# feu_35.net
KiCad netlist of a schematic drawn in EAGLE
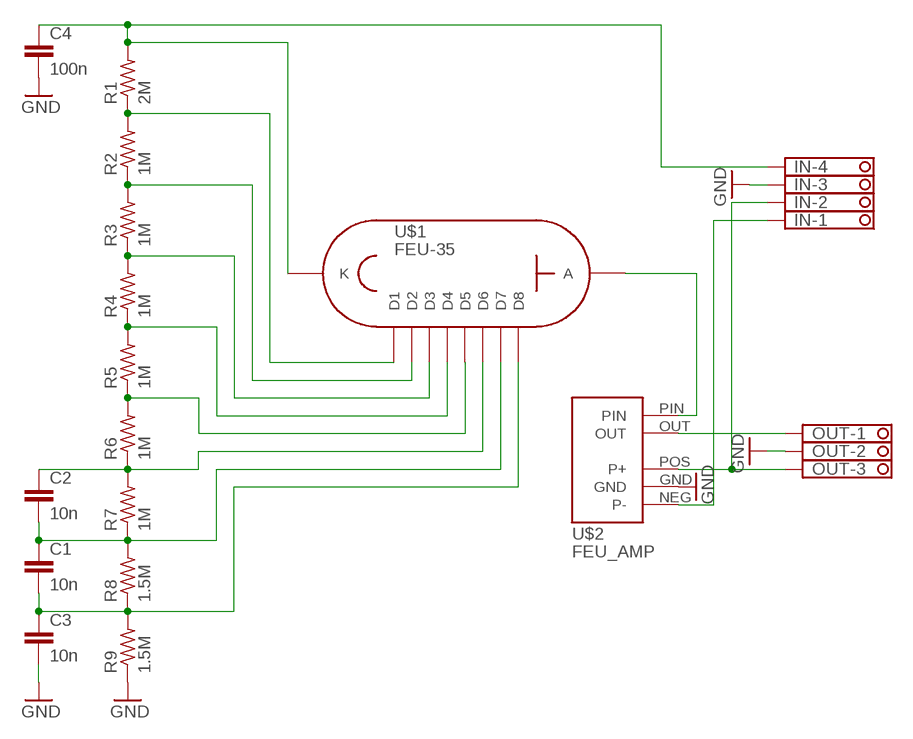
[diagram p0: schematic, sheet 1]

(export (version "E")
  (design (tool "Eeschema 10.0.6"))
  (components
    (comp (ref "C1")
      (value "10n")
      (footprint "eagle-import:C075-032X103")
      (libsource (lib "eagle-import") (part "C-EU075-032X103"))
    )
    (comp (ref "C2")
      (value "10n")
      (footprint "eagle-import:C075-032X103")
      (libsource (lib "eagle-import") (part "C-EU075-032X103"))
    )
    (comp (ref "C3")
      (value "10n")
      (footprint "eagle-import:C075-032X103")
      (libsource (lib "eagle-import") (part "C-EU075-032X103"))
    )
    (comp (ref "C4")
      (value "100n")
      (footprint "eagle-import:C225-087X268")
      (libsource (lib "eagle-import") (part "C-EU225-087X268"))
    )
    (comp (ref "IN")
      (value "1751264")
      (footprint "eagle-import:1751264")
      (libsource (lib "eagle-import") (part "1751264"))
    )
    (comp (ref "OUT")
      (value "1751251")
      (footprint "eagle-import:1751251")
      (libsource (lib "eagle-import") (part "1751251"))
    )
    (comp (ref "R1")
      (value "2M")
      (footprint "eagle-import:0207_2V")
      (libsource (lib "eagle-import") (part "R-US_0207/2V"))
    )
    (comp (ref "R2")
      (value "1M")
      (footprint "eagle-import:0207_2V")
      (libsource (lib "eagle-import") (part "R-US_0207/2V"))
    )
    (comp (ref "R3")
      (value "1M")
      (footprint "eagle-import:0207_2V")
      (libsource (lib "eagle-import") (part "R-US_0207/2V"))
    )
    (comp (ref "R4")
      (value "1M")
      (footprint "eagle-import:0207_2V")
      (libsource (lib "eagle-import") (part "R-US_0207/2V"))
    )
    (comp (ref "R5")
      (value "1M")
      (footprint "eagle-import:0207_2V")
      (libsource (lib "eagle-import") (part "R-US_0207/2V"))
    )
    (comp (ref "R6")
      (value "1M")
      (footprint "eagle-import:0207_2V")
      (libsource (lib "eagle-import") (part "R-US_0207/2V"))
    )
    (comp (ref "R7")
      (value "1M")
      (footprint "eagle-import:0207_2V")
      (libsource (lib "eagle-import") (part "R-US_0207/2V"))
    )
    (comp (ref "R8")
      (value "1.5M")
      (footprint "eagle-import:0207_2V")
      (libsource (lib "eagle-import") (part "R-US_0207/2V"))
    )
    (comp (ref "R9")
      (value "1.5M")
      (footprint "eagle-import:0207_2V")
      (libsource (lib "eagle-import") (part "R-US_0207/2V"))
    )
    (comp (ref "U$1")
      (value "FEU-35")
      (footprint "eagle-import:PANEL_10")
      (libsource (lib "eagle-import") (part "FEU-35"))
    )
    (comp (ref "U$2")
      (value "FEU_AMP")
      (footprint "eagle-import:FEU_AMP")
      (libsource (lib "eagle-import") (part "FEU_AMP"))
    )
  )
  (nets
    (net (code "1") (name "GND") (class "Default")
      (node (ref "C3") (pin "2") (pinfunction "2_2") (pintype "passive"))
      (node (ref "C4") (pin "2") (pinfunction "2_2") (pintype "passive"))
      (node (ref "IN") (pin "3") (pinfunction "K_3") (pintype "passive"))
      (node (ref "OUT") (pin "2") (pinfunction "K_2") (pintype "passive"))
      (node (ref "R9") (pin "1") (pinfunction "1_1") (pintype "passive"))
      (node (ref "U$2") (pin "GND") (pinfunction "GND_GND") (pintype "power_in"))
    )
    (net (code "2") (name "Net-(INA-K)") (class "Default")
      (node (ref "IN") (pin "1") (pinfunction "K_1") (pintype "passive"))
      (node (ref "U$2") (pin "NEG") (pinfunction "P-_NEG") (pintype "power_in"))
    )
    (net (code "3") (name "Net-(INB-K)") (class "Default")
      (node (ref "IN") (pin "2") (pinfunction "K_2") (pintype "passive"))
      (node (ref "OUT") (pin "3") (pinfunction "K_3") (pintype "passive"))
      (node (ref "U$2") (pin "POS") (pinfunction "P+_POS") (pintype "power_in"))
    )
    (net (code "4") (name "Net-(IND-K)") (class "Default")
      (node (ref "C4") (pin "1") (pinfunction "1_1") (pintype "passive"))
      (node (ref "IN") (pin "4") (pinfunction "K_4") (pintype "passive"))
      (node (ref "R1") (pin "2") (pinfunction "2_2") (pintype "passive"))
      (node (ref "U$1") (pin "P$1") (pinfunction "K_P$1") (pintype "input"))
    )
    (net (code "5") (name "Net-(OUTA-K)") (class "Default")
      (node (ref "OUT") (pin "1") (pinfunction "K_1") (pintype "passive"))
      (node (ref "U$2") (pin "OUT") (pinfunction "OUT_OUT") (pintype "output"))
    )
    (net (code "6") (name "Net-(U$1-A)") (class "Default")
      (node (ref "U$1") (pin "P$10") (pinfunction "A_P$10") (pintype "output"))
      (node (ref "U$2") (pin "PIN") (pinfunction "PIN_PIN") (pintype "input"))
    )
    (net (code "7") (name "Net-(U$1-D1)") (class "Default")
      (node (ref "R1") (pin "1") (pinfunction "1_1") (pintype "passive"))
      (node (ref "R2") (pin "2") (pinfunction "2_2") (pintype "passive"))
      (node (ref "U$1") (pin "P$2") (pinfunction "D1_P$2") (pintype "input"))
    )
    (net (code "8") (name "Net-(U$1-D2)") (class "Default")
      (node (ref "R2") (pin "1") (pinfunction "1_1") (pintype "passive"))
      (node (ref "R3") (pin "2") (pinfunction "2_2") (pintype "passive"))
      (node (ref "U$1") (pin "P$3") (pinfunction "D2_P$3") (pintype "input"))
    )
    (net (code "9") (name "Net-(U$1-D3)") (class "Default")
      (node (ref "R3") (pin "1") (pinfunction "1_1") (pintype "passive"))
      (node (ref "R4") (pin "2") (pinfunction "2_2") (pintype "passive"))
      (node (ref "U$1") (pin "P$4") (pinfunction "D3_P$4") (pintype "input"))
    )
    (net (code "10") (name "Net-(U$1-D4)") (class "Default")
      (node (ref "R4") (pin "1") (pinfunction "1_1") (pintype "passive"))
      (node (ref "R5") (pin "2") (pinfunction "2_2") (pintype "passive"))
      (node (ref "U$1") (pin "P$5") (pinfunction "D4_P$5") (pintype "input"))
    )
    (net (code "11") (name "Net-(U$1-D5)") (class "Default")
      (node (ref "R5") (pin "1") (pinfunction "1_1") (pintype "passive"))
      (node (ref "R6") (pin "2") (pinfunction "2_2") (pintype "passive"))
      (node (ref "U$1") (pin "P$6") (pinfunction "D5_P$6") (pintype "input"))
    )
    (net (code "12") (name "Net-(U$1-D6)") (class "Default")
      (node (ref "C2") (pin "1") (pinfunction "1_1") (pintype "passive"))
      (node (ref "R6") (pin "1") (pinfunction "1_1") (pintype "passive"))
      (node (ref "R7") (pin "2") (pinfunction "2_2") (pintype "passive"))
      (node (ref "U$1") (pin "P$7") (pinfunction "D6_P$7") (pintype "input"))
    )
    (net (code "13") (name "Net-(U$1-D7)") (class "Default")
      (node (ref "C1") (pin "1") (pinfunction "1_1") (pintype "passive"))
      (node (ref "C2") (pin "2") (pinfunction "2_2") (pintype "passive"))
      (node (ref "R7") (pin "1") (pinfunction "1_1") (pintype "passive"))
      (node (ref "R8") (pin "2") (pinfunction "2_2") (pintype "passive"))
      (node (ref "U$1") (pin "P$8") (pinfunction "D7_P$8") (pintype "input"))
    )
    (net (code "14") (name "Net-(U$1-D8)") (class "Default")
      (node (ref "C1") (pin "2") (pinfunction "2_2") (pintype "passive"))
      (node (ref "C3") (pin "1") (pinfunction "1_1") (pintype "passive"))
      (node (ref "R8") (pin "1") (pinfunction "1_1") (pintype "passive"))
      (node (ref "R9") (pin "2") (pinfunction "2_2") (pintype "passive"))
      (node (ref "U$1") (pin "P$9") (pinfunction "D8_P$9") (pintype "input"))
    )
  )
)
